# power.net
KiCad netlist of a schematic drawn in Altium Designer
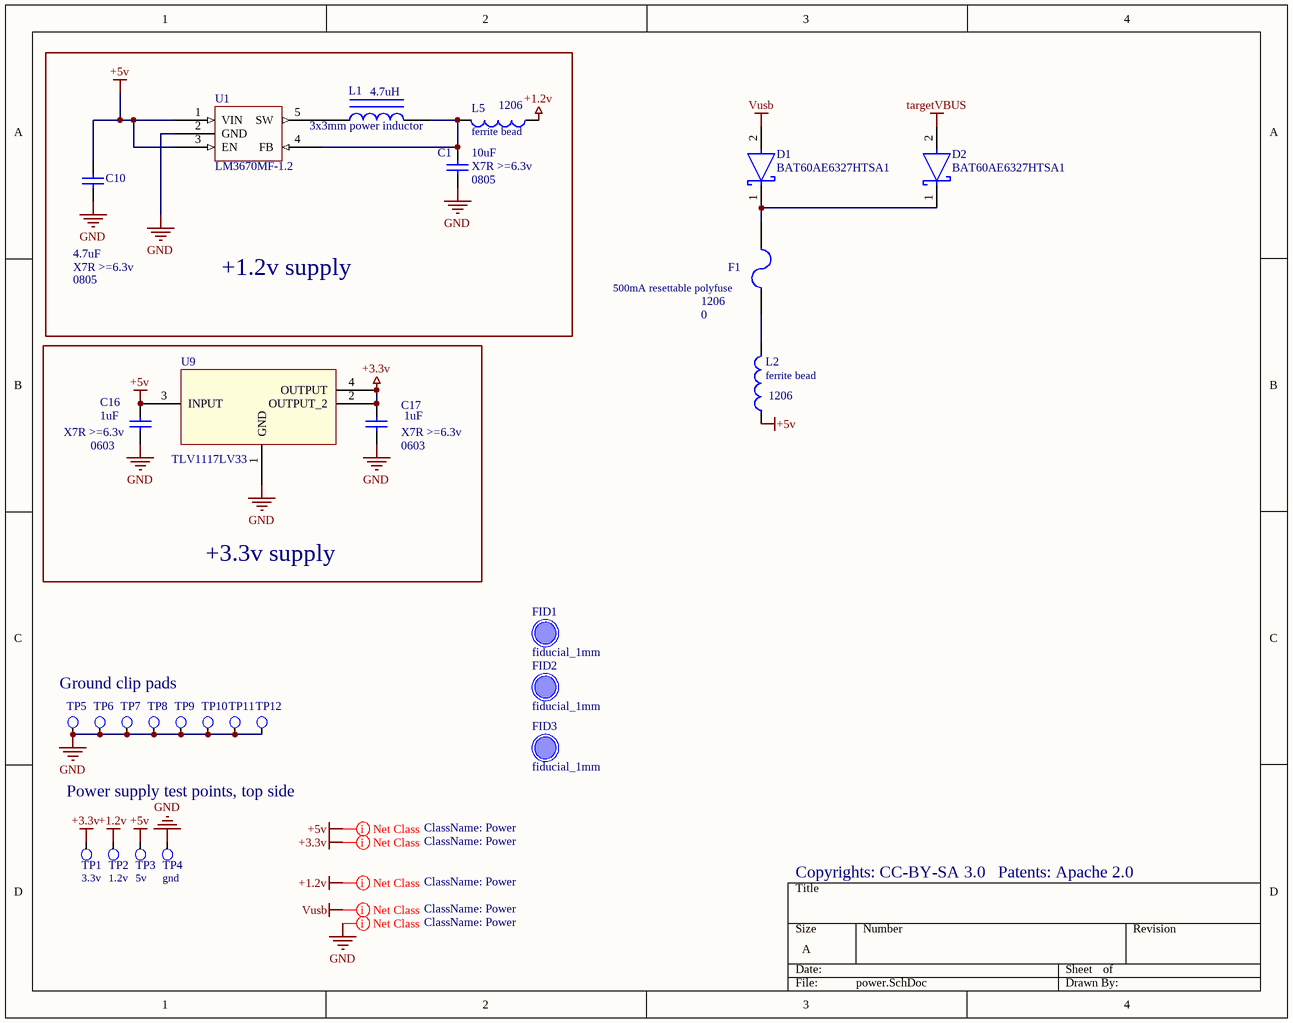
[diagram p0: power.SchDoc]

(export (version "E")
  (design (tool "Eeschema 10.0.6"))
  (components
    (comp (ref "C1")
      (value "10uF")
      (footprint "CAPC2012N")
      (description "Capacitor (Semiconductor SIM Model)")
      (fields
        (field (name "PACKAGEREFERENCE") "0805")
        (field (name "TOLERANCE") "±10%")
        (field (name "RATING") "X7R >=6.3v")
        (field (name "Comment") "Cap Semi")
      )
      (libsource (lib "Miscellaneous Devices") (part "Cap Semi"))
    )
    (comp (ref "C10")
      (value "4.7uF")
      (footprint "CAPC2012N")
      (description "Capacitor")
      (fields
        (field (name "PACKAGEREFERENCE") "0805")
        (field (name "TOLERANCE") "-20%, +80%")
        (field (name "RATING") "X7R >=6.3v")
        (field (name "Comment") "Cap Semi")
      )
      (libsource (lib "Miscellaneous Devices") (part "Cap"))
    )
    (comp (ref "C16")
      (value "1uF")
      (footprint "Chip_Capacitor_N:CAPC1608N")
      (description "Capacitor (Semiconductor SIM Model)")
      (fields
        (field (name "PACKAGEREFERENCE") "0603")
        (field (name "RATING") "X7R >=6.3v")
        (field (name "Comment") "Cap Semi")
      )
      (libsource (lib "Miscellaneous Devices") (part "Cap Semi"))
    )
    (comp (ref "C17")
      (value "1uF")
      (footprint "Chip_Capacitor_N:CAPC1608N")
      (description "Capacitor (Semiconductor SIM Model)")
      (fields
        (field (name "PACKAGEREFERENCE") "0603")
        (field (name "RATING") "X7R >=6.3v")
        (field (name "Comment") "Cap Semi")
      )
      (libsource (lib "Miscellaneous Devices") (part "Cap Semi"))
    )
    (comp (ref "D1")
      (value "BAT60AE6327HTSA1")
      (footprint "FP-PG-SOD323-2-IPC_C")
      (description "DIODE SCHOTTKY 10V 3A SOD323-2")
      (libsource (lib "Altium Content Vault") (part "1d6ec82d83fb6aee721767c19dac4b9"))
    )
    (comp (ref "D2")
      (value "BAT60AE6327HTSA1")
      (footprint "FP-PG-SOD323-2-IPC_C")
      (description "DIODE SCHOTTKY 10V 3A SOD323-2")
      (libsource (lib "Altium Content Vault") (part "1d6ec82d83fb6aee721767c19dac4b9"))
    )
    (comp (ref "F1")
      (value "500mA resettable polyfuse")
      (footprint "RESC3216N")
      (description "Fuse")
      (fields (field (name "PACKAGEREFERENCE") "1206") (field (name "ALTIUM_VALUE") "0"))
      (libsource (lib "Miscellaneous Devices") (part "Fuse 2"))
    )
    (comp (ref "FID1")
      (value "fiducial_1mm")
      (footprint "Fiducial_1mm")
      (libsource (lib "ov_ftdi") (part "fiducial_1mm"))
    )
    (comp (ref "FID2")
      (value "fiducial_1mm")
      (footprint "Fiducial_1mm")
      (libsource (lib "ov_ftdi") (part "fiducial_1mm"))
    )
    (comp (ref "FID3")
      (value "fiducial_1mm")
      (footprint "Fiducial_1mm")
      (libsource (lib "ov_ftdi") (part "fiducial_1mm"))
    )
    (comp (ref "L1")
      (value "3x3mm power inductor")
      (footprint "3x3mm inductor")
      (description "Magnetic-Core Inductor")
      (fields (field (name "ALTIUM_VALUE") "4.7uH"))
      (libsource (lib "Miscellaneous Devices") (part "Inductor Iron"))
    )
    (comp (ref "L2")
      (value "ferrite bead")
      (footprint "INDC3216AN")
      (description "Inductor")
      (fields (field (name "PACKAGEREFERENCE") "1206"))
      (libsource (lib "Miscellaneous Devices") (part "Inductor"))
    )
    (comp (ref "L5")
      (value "ferrite bead")
      (footprint "INDC3216N")
      (description "Inductor")
      (fields (field (name "PACKAGEREFERENCE") "1206"))
      (libsource (lib "Miscellaneous Devices") (part "Inductor"))
    )
    (comp (ref "TP1")
      (value "3.3v")
      (footprint "testpoint-60mil")
      (description "PCB test point")
      (libsource (lib "ov_ftdi") (part "Test Pad"))
    )
    (comp (ref "TP2")
      (value "1.2v")
      (footprint "testpoint-60mil")
      (description "PCB test point")
      (libsource (lib "ov_ftdi") (part "Test Pad"))
    )
    (comp (ref "TP3")
      (value "5v")
      (footprint "testpoint-60mil")
      (description "PCB test point")
      (libsource (lib "ov_ftdi") (part "Test Pad"))
    )
    (comp (ref "TP4")
      (value "gnd")
      (footprint "testpoint-60mil")
      (description "PCB test point")
      (libsource (lib "ov_ftdi") (part "Test Pad"))
    )
    (comp (ref "TP5")
      (value "~")
      (footprint "ground pad")
      (description "PCB test point")
      (libsource (lib "OpenVizsla symbols") (part "Test Pad"))
    )
    (comp (ref "TP6")
      (value "~")
      (footprint "ground pad")
      (description "PCB test point")
      (libsource (lib "OpenVizsla symbols") (part "Test Pad"))
    )
    (comp (ref "TP7")
      (value "~")
      (footprint "ground pad")
      (description "PCB test point")
      (libsource (lib "OpenVizsla symbols") (part "Test Pad"))
    )
    (comp (ref "TP8")
      (value "~")
      (footprint "ground pad")
      (description "PCB test point")
      (libsource (lib "OpenVizsla symbols") (part "Test Pad"))
    )
    (comp (ref "TP9")
      (value "~")
      (footprint "ground pad")
      (description "PCB test point")
      (libsource (lib "OpenVizsla symbols") (part "Test Pad"))
    )
    (comp (ref "TP10")
      (value "~")
      (footprint "ground pad")
      (description "PCB test point")
      (libsource (lib "OpenVizsla symbols") (part "Test Pad"))
    )
    (comp (ref "TP11")
      (value "~")
      (footprint "ground pad")
      (description "PCB test point")
      (libsource (lib "OpenVizsla symbols") (part "Test Pad"))
    )
    (comp (ref "TP12")
      (value "~")
      (footprint "ground pad")
      (description "PCB test point")
      (libsource (lib "OpenVizsla symbols") (part "Test Pad"))
    )
    (comp (ref "U1")
      (value "LM3670MF-1.2")
      (footprint "SOT23-5AN")
      (description "LM3670 buck step-down regulator, 350 mA")
      (fields (field (name "Comment") "LM3670MF-1.2/NOPB"))
      (libsource (lib "*") (part "LM3670"))
    )
    (comp (ref "U9")
      (value "TLV1117LV33")
      (footprint "DCY4")
      (libsource (lib "OpenVizsla symbols") (part "TLV1117"))
    )
  )
  (nets
    (net (code "1") (name "+1.2v") (class "Default")
      (node (ref "L5") (pin "1") (pinfunction "1_1") (pintype "passive"))
      (node (ref "TP2") (pin "1") (pinfunction "pin_1") (pintype "passive"))
    )
    (net (code "2") (name "+3.3v") (class "Default")
      (node (ref "C17") (pin "2") (pinfunction "2_2") (pintype "passive"))
      (node (ref "TP1") (pin "1") (pinfunction "pin_1") (pintype "passive"))
      (node (ref "U9") (pin "2") (pinfunction "OUTPUT_2_2") (pintype "power_in"))
      (node (ref "U9") (pin "4") (pinfunction "OUTPUT_4") (pintype "power_in"))
    )
    (net (code "3") (name "+5v") (class "Default")
      (node (ref "C10") (pin "2") (pinfunction "2_2") (pintype "passive"))
      (node (ref "C16") (pin "2") (pinfunction "2_2") (pintype "passive"))
      (node (ref "L2") (pin "1") (pinfunction "1_1") (pintype "passive"))
      (node (ref "TP3") (pin "1") (pinfunction "pin_1") (pintype "passive"))
      (node (ref "U1") (pin "1") (pinfunction "VIN_1") (pintype "input"))
      (node (ref "U1") (pin "3") (pinfunction "EN_3") (pintype "input"))
      (node (ref "U9") (pin "3") (pinfunction "INPUT_3") (pintype "power_in"))
    )
    (net (code "4") (name "GND") (class "Default")
      (node (ref "C1") (pin "1") (pinfunction "1_1") (pintype "passive"))
      (node (ref "C10") (pin "1") (pinfunction "1_1") (pintype "passive"))
      (node (ref "C16") (pin "1") (pinfunction "1_1") (pintype "passive"))
      (node (ref "C17") (pin "1") (pinfunction "1_1") (pintype "passive"))
      (node (ref "TP10") (pin "1") (pinfunction "pin_1") (pintype "passive"))
      (node (ref "TP11") (pin "1") (pinfunction "pin_1") (pintype "passive"))
      (node (ref "TP12") (pin "1") (pinfunction "pin_1") (pintype "passive"))
      (node (ref "TP4") (pin "1") (pinfunction "pin_1") (pintype "passive"))
      (node (ref "TP5") (pin "1") (pinfunction "pin_1") (pintype "passive"))
      (node (ref "TP6") (pin "1") (pinfunction "pin_1") (pintype "passive"))
      (node (ref "TP7") (pin "1") (pinfunction "pin_1") (pintype "passive"))
      (node (ref "TP8") (pin "1") (pinfunction "pin_1") (pintype "passive"))
      (node (ref "TP9") (pin "1") (pinfunction "pin_1") (pintype "passive"))
      (node (ref "U1") (pin "2") (pinfunction "GND_2") (pintype "power_in"))
      (node (ref "U9") (pin "1") (pinfunction "GND_1") (pintype "power_in"))
    )
    (net (code "5") (name "Net-(D1-C)") (class "Default")
      (node (ref "D1") (pin "1") (pinfunction "C_1") (pintype "passive"))
      (node (ref "D2") (pin "1") (pinfunction "C_1") (pintype "passive"))
      (node (ref "F1") (pin "1") (pinfunction "1_1") (pintype "passive"))
    )
    (net (code "6") (name "Net-(F1-Pad2)") (class "Default")
      (node (ref "F1") (pin "2") (pinfunction "2_2") (pintype "passive"))
      (node (ref "L2") (pin "2") (pinfunction "2_2") (pintype "passive"))
    )
    (net (code "7") (name "Net-(U1-FB)") (class "Default")
      (node (ref "C1") (pin "2") (pinfunction "2_2") (pintype "passive"))
      (node (ref "L1") (pin "2") (pinfunction "2_2") (pintype "passive"))
      (node (ref "L5") (pin "2") (pinfunction "2_2") (pintype "passive"))
      (node (ref "U1") (pin "4") (pinfunction "FB_4") (pintype "input"))
    )
    (net (code "8") (name "Net-(U1-SW)") (class "Default")
      (node (ref "L1") (pin "1") (pinfunction "1_1") (pintype "passive"))
      (node (ref "U1") (pin "5") (pinfunction "SW_5") (pintype "output"))
    )
    (net (code "9") (name "Vusb") (class "Default")
      (node (ref "D1") (pin "2") (pinfunction "A_2") (pintype "passive"))
    )
    (net (code "10") (name "targetVBUS") (class "Default")
      (node (ref "D2") (pin "2") (pinfunction "A_2") (pintype "passive"))
    )
  )
)
